# ac-dc_brd_2014-10-22.net
KiCad netlist of a schematic drawn in EAGLE
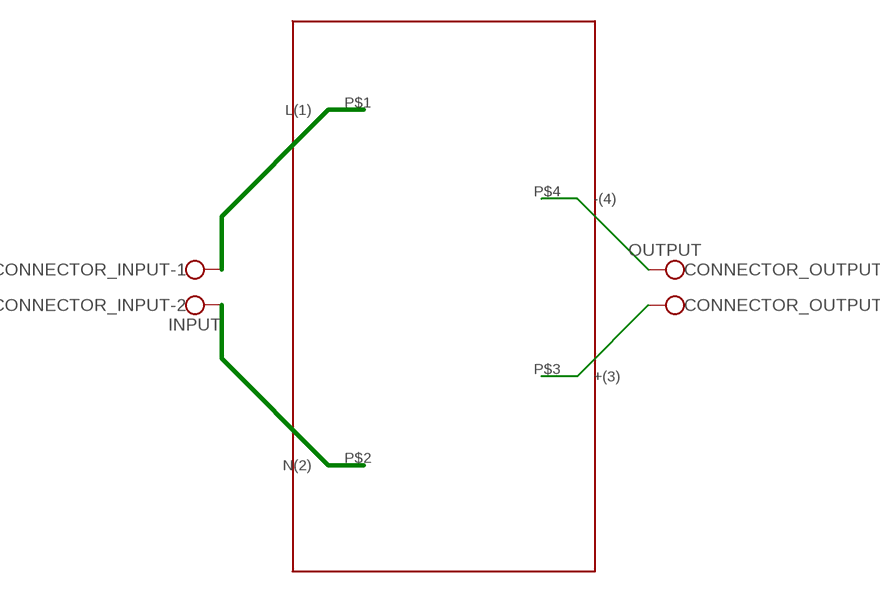
[diagram p0: schematic, sheet 1]

(export (version "E")
  (design (tool "Eeschema 10.0.6"))
  (components
    (comp (ref "CONNECTOR_INPUT")
      (value "INPUT")
      (footprint "eagle-import:W237-102")
      (fields (field (name "MPN") "237-102") (field (name "MF") "INPUT"))
      (libsource (lib "eagle-import") (part "W237-102"))
    )
    (comp (ref "CONNECTOR_OUTPUT")
      (value "OUTPUT")
      (footprint "eagle-import:W237-102")
      (fields (field (name "MPN") "237-102"))
      (libsource (lib "eagle-import") (part "W237-102"))
    )
    (comp (ref "U$2")
      (value "VTX_214")
      (footprint "eagle-import:VTX-214-005")
      (libsource (lib "eagle-import") (part "VTX_214"))
    )
  )
  (nets
    (net (code "1") (name "Net-(CONNECTOR_INPUTA-KL)") (class "Default")
      (node (ref "CONNECTOR_INPUT") (pin "1") (pinfunction "KL_1") (pintype "passive"))
      (node (ref "U$2") (pin "P$1") (pinfunction "L(1)_P$1") (pintype "input"))
    )
    (net (code "2") (name "Net-(CONNECTOR_INPUTB-KL)") (class "Default")
      (node (ref "CONNECTOR_INPUT") (pin "2") (pinfunction "KL_2") (pintype "passive"))
      (node (ref "U$2") (pin "P$2") (pinfunction "N(2)_P$2") (pintype "input"))
    )
    (net (code "3") (name "Net-(CONNECTOR_OUTPUTA-KL)") (class "Default")
      (node (ref "CONNECTOR_OUTPUT") (pin "1") (pinfunction "KL_1") (pintype "passive"))
      (node (ref "U$2") (pin "P$3") (pinfunction "+(3)_P$3") (pintype "output"))
    )
    (net (code "4") (name "Net-(CONNECTOR_OUTPUTB-KL)") (class "Default")
      (node (ref "CONNECTOR_OUTPUT") (pin "2") (pinfunction "KL_2") (pintype "passive"))
      (node (ref "U$2") (pin "P$4") (pinfunction "-(4)_P$4") (pintype "output"))
    )
  )
)
